# JacdacBrainNRF_57.net
KiCad netlist of a schematic drawn in Altium Designer
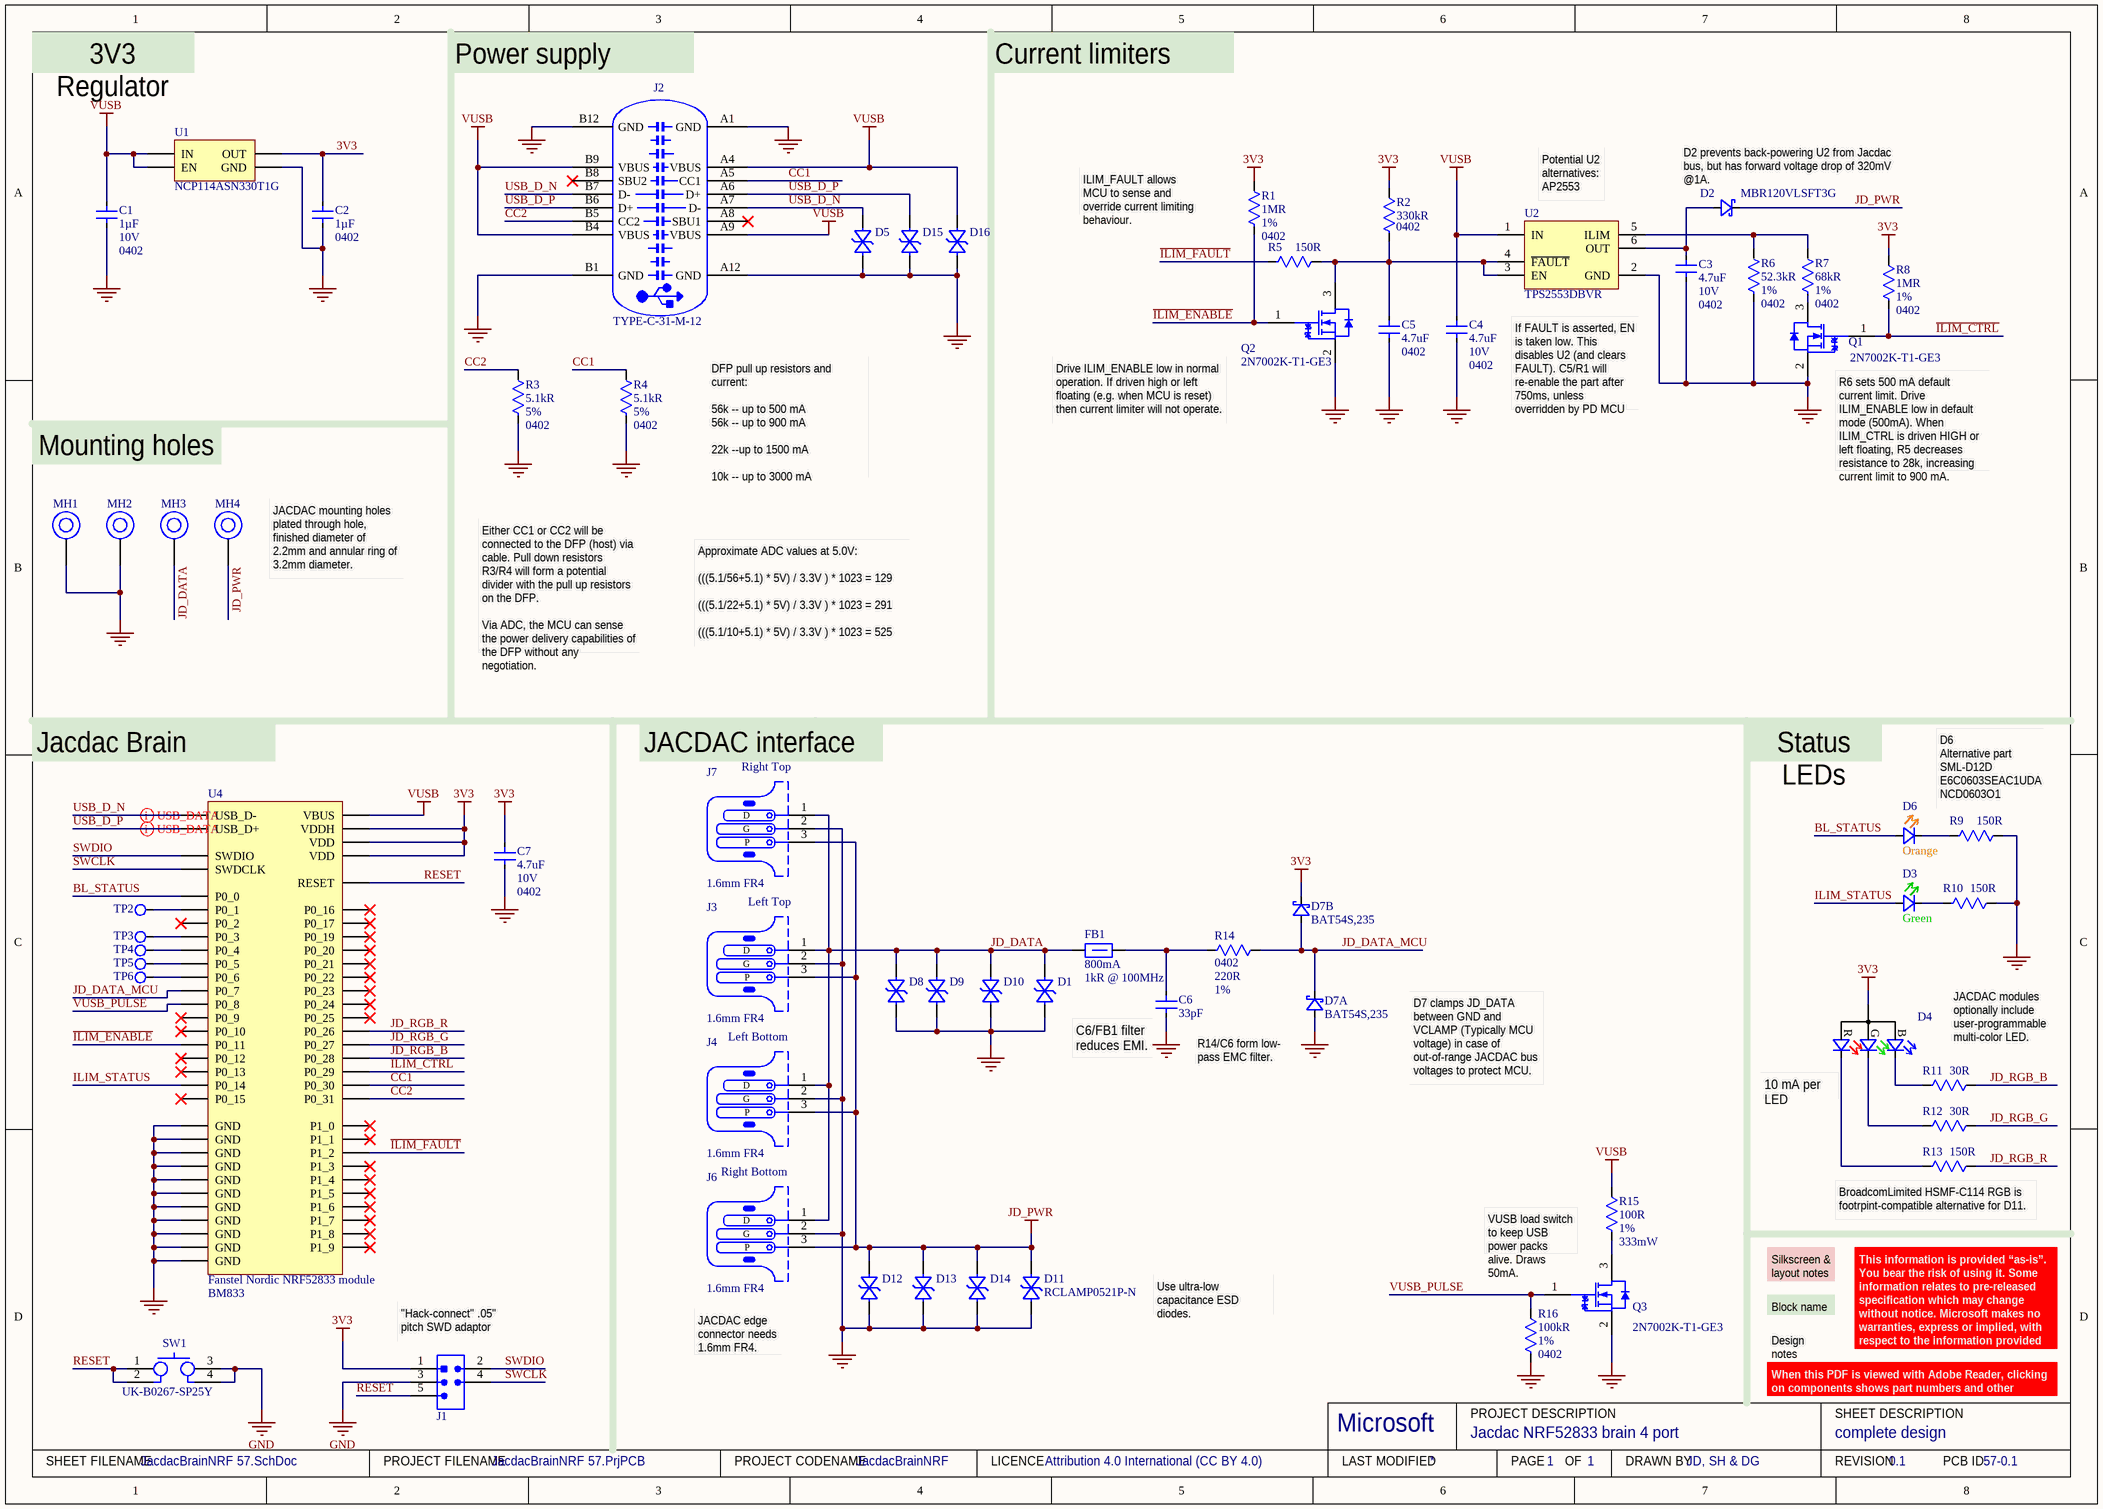
[diagram p0: JacdacBrainNRF 57.SchDoc]

(export (version "E")
  (design (tool "Eeschema 10.0.6"))
  (components
    (comp (ref "C1")
      (value "CL05A105KP5NNNC")
      (footprint "C0402_0.55MM - without outline")
      (description "CAP CER 1UF 10V X5R 0402")
      (fields
        (field (name "MANUFACTURER") "Samsung")
        (field (name "TOLERANCE") "10%")
        (field (name "CAPACITANCE") "1µF")
        (field (name "VOLTAGE RATING") "10V")
        (field (name "CASE CODE (IMPERIAL)") "0402")
        (field (name "CREATED") "DG")
        (field (name "CHECKED") "?")
      )
      (libsource (lib "Samsung") (part "CL05A105KP5NNNC"))
    )
    (comp (ref "C2")
      (value "CL05A105KP5NNNC")
      (footprint "C0402_0.55MM - without outline")
      (description "CAP CER 1UF 10V X5R 0402")
      (fields
        (field (name "MANUFACTURER") "Samsung")
        (field (name "TOLERANCE") "10%")
        (field (name "CAPACITANCE") "1µF")
        (field (name "CASE CODE (IMPERIAL)") "0402")
        (field (name "CREATED") "DG")
        (field (name "CHECKED") "?")
      )
      (libsource (lib "Samsung") (part "CL05A105KP5NNNC"))
    )
    (comp (ref "C3")
      (value "CL05A475MP5NRNC")
      (footprint "R0402 - Without outline")
      (description "CAP CER 4.7UF 10V X5R 0402")
      (fields
        (field (name "MANUFACTURER") "Samsung")
        (field (name "TOLERANCE") "20%")
        (field (name "CAPACITANCE") "4.7uF")
        (field (name "VOLTAGE RATING") "10V")
        (field (name "CASE CODE (IMPERIAL)") "0402")
        (field (name "CREATED BY") "D. Gakure")
        (field (name "CHECKED BY") "?")
      )
      (libsource (lib "Samsung") (part "CL05A475MP5NRNC"))
    )
    (comp (ref "C4")
      (value "CL05A475MP5NRNC")
      (footprint "R0402 - Without outline")
      (description "CAP CER 4.7UF 10V X5R 0402")
      (fields
        (field (name "MANUFACTURER") "Samsung")
        (field (name "TOLERANCE") "20%")
        (field (name "CAPACITANCE") "4.7uF")
        (field (name "VOLTAGE RATING") "10V")
        (field (name "CASE CODE (IMPERIAL)") "0402")
        (field (name "CREATED BY") "D. Gakure")
        (field (name "CHECKED BY") "?")
      )
      (libsource (lib "Samsung") (part "CL05A475MP5NRNC"))
    )
    (comp (ref "C5")
      (value "CL05A475MP5NRNC")
      (footprint "R0402 - Without outline")
      (description "CAP CER 4.7UF 10V X5R 0402")
      (fields
        (field (name "MANUFACTURER") "Samsung")
        (field (name "TOLERANCE") "20%")
        (field (name "CAPACITANCE") "4.7uF")
        (field (name "CASE CODE (IMPERIAL)") "0402")
        (field (name "CREATED BY") "D. Gakure")
        (field (name "CHECKED BY") "?")
      )
      (libsource (lib "Samsung") (part "CL05A475MP5NRNC"))
    )
    (comp (ref "C6")
      (value "CL05C330JB51PNC")
      (footprint "C0402_0.55MM - without outline")
      (description "CAP CER 33PF 50V NP0 0402")
      (fields
        (field (name "MANUFACTURER") "Samsung")
        (field (name "TOLERANCE") "5%")
        (field (name "CAPACITANCE") "33pF")
        (field (name "CHECKED") "?")
        (field (name "CREATED") "DG")
      )
      (libsource (lib "Samsung") (part "CL05C330JB51PNC"))
    )
    (comp (ref "C7")
      (value "CL05A475MP5NRNC")
      (footprint "R0402 - Without outline")
      (description "CAP CER 4.7UF 10V X5R 0402")
      (fields
        (field (name "MANUFACTURER") "Samsung")
        (field (name "TOLERANCE") "20%")
        (field (name "CAPACITANCE") "4.7uF")
        (field (name "VOLTAGE RATING") "10V")
        (field (name "CASE CODE (IMPERIAL)") "0402")
        (field (name "CREATED BY") "D. Gakure")
        (field (name "CHECKED BY") "?")
      )
      (libsource (lib "Samsung") (part "CL05A475MP5NRNC"))
    )
    (comp (ref "D1")
      (value "RCLAMP0521P-N")
      (footprint "TVS 0402 - L")
      (description "Bidirectional 5V (Max) 6V 16V 3.5A (8/20us) 0402 TVS RoHS")
      (fields
        (field (name "MANUFACTURER") "Born Semiconductor")
        (field (name "CREATED BY") "D Gakure")
        (field (name "CHECKED BY") "?")
      )
      (libsource (lib "BornSemiconductor") (part "RCLAMP0521P-N"))
    )
    (comp (ref "D2")
      (value "MBR120VLSFT3G")
      (footprint "MBR120VLSFT3G")
      (description "DIODE SCHOTTKY 20V 1A SOD123FL")
      (fields
        (field (name "MANUFACTURER") "ON Semiconductor")
        (field (name "MANUFACTURER PART NUMBER") "MBR120VLSFT3G")
      )
      (libsource (lib "OnSemiconductor") (part "MBR120VLSFT3G"))
    )
    (comp (ref "D3")
      (value "~")
      (footprint "0603 Green")
      (description "LED GREEN DIFFUSED 0603 SMD")
      (fields
        (field (name "MANUFACTURER") "Everlight Elec")
        (field (name "MANUFACTURER PART NUMBER") "19-217/GHC-YR1S2/3T")
        (field (name "COLOUR") "Green")
      )
      (libsource (lib "EverlightElec") (part "19-217/GHC-YR1S2/3T"))
    )
    (comp (ref "D4")
      (value "TZ-P4-1615RGBTCA1-0.55T")
      (footprint "TZ-P4-1615RGBTCA1-0.55T")
      (description "1615 Light Emitting Diodes (LED) RoHS")
      (fields
        (field (name "MANUFACTURER") "TUOZHAN")
        (field (name "CREATED BY") "D. Gakure")
        (field (name "CHECKED BY") "?")
      )
      (libsource (lib "Tuozhan") (part "TZ-P4-1615RGBTCA1-0.55T"))
    )
    (comp (ref "D5")
      (value "RCLAMP0521P-N")
      (footprint "TVS 0402 - L")
      (description "Bidirectional 5V (Max) 6V 16V 3.5A (8/20us) 0402 TVS RoHS")
      (fields
        (field (name "MANUFACTURER") "Born Semiconductor")
        (field (name "CREATED BY") "D Gakure")
        (field (name "CHECKED BY") "?")
      )
      (libsource (lib "BornSemiconductor") (part "RCLAMP0521P-N"))
    )
    (comp (ref "D6")
      (value "~")
      (footprint "0603 Orange")
      (description "LED ORANGE DIFFUSED 0603 SMD")
      (fields
        (field (name "MANUFACTURER") "Everlight Elec")
        (field (name "MANUFACTURER PART NUMBER") "19-217/S2C-AQ1R1B/3T")
        (field (name "COLOUR") "Orange")
      )
      (libsource (lib "EverlightElec") (part "19-217/S2C-AQ1R1B/3T"))
    )
    (comp (ref "D7")
      (value "BAT54S")
      (footprint "NXP-BAT54S-TO-236AB")
      (description "DIODE ARRAY SCHOTTKY 30V SOT23")
      (fields (field (name "MANUFACTURER") "Nexperia") (field (name "MANUFACTURER PART NUMBER") "BAT54S,235"))
      (libsource (lib "NXP") (part "BAT54S"))
    )
    (comp (ref "D8")
      (value "RCLAMP0521P-N")
      (footprint "TVS 0402 - L")
      (description "Bidirectional 5V (Max) 6V 16V 3.5A (8/20us) 0402 TVS RoHS")
      (fields
        (field (name "MANUFACTURER") "Born Semiconductor")
        (field (name "CREATED BY") "D Gakure")
        (field (name "CHECKED BY") "?")
      )
      (libsource (lib "BornSemiconductor") (part "RCLAMP0521P-N"))
    )
    (comp (ref "D9")
      (value "RCLAMP0521P-N")
      (footprint "TVS 0402 - L")
      (description "Bidirectional 5V (Max) 6V 16V 3.5A (8/20us) 0402 TVS RoHS")
      (fields
        (field (name "MANUFACTURER") "Born Semiconductor")
        (field (name "CREATED BY") "D Gakure")
        (field (name "CHECKED BY") "?")
      )
      (libsource (lib "BornSemiconductor") (part "RCLAMP0521P-N"))
    )
    (comp (ref "D10")
      (value "RCLAMP0521P-N")
      (footprint "TVS 0402 - L")
      (description "Bidirectional 5V (Max) 6V 16V 3.5A (8/20us) 0402 TVS RoHS")
      (fields
        (field (name "MANUFACTURER") "Born Semiconductor")
        (field (name "CREATED BY") "D Gakure")
        (field (name "CHECKED BY") "?")
      )
      (libsource (lib "BornSemiconductor") (part "RCLAMP0521P-N"))
    )
    (comp (ref "D11")
      (value "RCLAMP0521P-N")
      (footprint "TVS 0402 - L")
      (description "Bidirectional 5V (Max) 6V 16V 3.5A (8/20us) 0402 TVS RoHS")
      (fields
        (field (name "MANUFACTURER") "Born Semiconductor")
        (field (name "MANUFACTURER PART NUMBER") "RCLAMP0521P-N")
        (field (name "CREATED BY") "D Gakure")
        (field (name "CHECKED BY") "?")
      )
      (libsource (lib "BornSemiconductor") (part "RCLAMP0521P-N"))
    )
    (comp (ref "D12")
      (value "RCLAMP0521P-N")
      (footprint "TVS 0402 - L")
      (description "Bidirectional 5V (Max) 6V 16V 3.5A (8/20us) 0402 TVS RoHS")
      (fields
        (field (name "MANUFACTURER") "Born Semiconductor")
        (field (name "CREATED BY") "D Gakure")
        (field (name "CHECKED BY") "?")
      )
      (libsource (lib "BornSemiconductor") (part "RCLAMP0521P-N"))
    )
    (comp (ref "D13")
      (value "RCLAMP0521P-N")
      (footprint "TVS 0402 - L")
      (description "Bidirectional 5V (Max) 6V 16V 3.5A (8/20us) 0402 TVS RoHS")
      (fields
        (field (name "MANUFACTURER") "Born Semiconductor")
        (field (name "CREATED BY") "D Gakure")
        (field (name "CHECKED BY") "?")
      )
      (libsource (lib "BornSemiconductor") (part "RCLAMP0521P-N"))
    )
    (comp (ref "D14")
      (value "RCLAMP0521P-N")
      (footprint "TVS 0402 - L")
      (description "Bidirectional 5V (Max) 6V 16V 3.5A (8/20us) 0402 TVS RoHS")
      (fields
        (field (name "MANUFACTURER") "Born Semiconductor")
        (field (name "CREATED BY") "D Gakure")
        (field (name "CHECKED BY") "?")
      )
      (libsource (lib "BornSemiconductor") (part "RCLAMP0521P-N"))
    )
    (comp (ref "D15")
      (value "RCLAMP0521P-N")
      (footprint "TVS 0402 - L")
      (description "Bidirectional 5V (Max) 6V 16V 3.5A (8/20us) 0402 TVS RoHS")
      (fields
        (field (name "MANUFACTURER") "Born Semiconductor")
        (field (name "CREATED BY") "D Gakure")
        (field (name "CHECKED BY") "?")
      )
      (libsource (lib "BornSemiconductor") (part "RCLAMP0521P-N"))
    )
    (comp (ref "D16")
      (value "RCLAMP0521P-N")
      (footprint "TVS 0402 - L")
      (description "Bidirectional 5V (Max) 6V 16V 3.5A (8/20us) 0402 TVS RoHS")
      (fields
        (field (name "MANUFACTURER") "Born Semiconductor")
        (field (name "CREATED BY") "D Gakure")
        (field (name "CHECKED BY") "?")
      )
      (libsource (lib "BornSemiconductor") (part "RCLAMP0521P-N"))
    )
    (comp (ref "FB1")
      (value "TDK MPZ1608S102ATA00")
      (footprint "TDK MPZ1608 0.8mm - without outline")
      (description "0603 1k@100MHz 0.8A chip")
      (fields
        (field (name "TOLERANCE") "25%")
        (field (name "MANUFACTURER") "TDK")
        (field (name "CURRENT RATING") "800mA")
        (field (name "IMPEDANCE") "1kR @ 100MHz")
      )
      (libsource (lib "TDK") (part "TDK MPZ1608S102ATA00"))
    )
    (comp (ref "J1")
      (value "Hack Connect Mini 1.27 mm pitch 2-row")
      (footprint "HACK_CONNECT_MINI_5_X_1_27")
      (libsource (lib "generic-con") (part "HACK_CONNECT_MINI"))
    )
    (comp (ref "J2")
      (value "TYPE-C-31-M-12")
      (footprint "TYPE-C-31-M-12")
      (description "USB - Type C Female 16 USB Connectors RoHS")
      (fields
        (field (name "MANUFACTURER") "Korean Hroparts Elec")
        (field (name "MANUFACTURER PART NUMBER") "TYPE-C-31-M-12")
      )
      (libsource (lib "KoreanHropartsElec") (part "TYPE-C-31-M-12"))
    )
    (comp (ref "J3")
      (value "3 pin JACDAC edge connector")
      (footprint "JACDAC_EDGE_CONNECTOR_NO_TRACES")
      (description "3 pin Jacdac edge connector 1.27mm pitch")
      (fields
        (field (name "MANUFACTURER PART NUMBER") "JACDAC_EDGE_CONNECTOR")
        (field (name "PCB TYPE") "1.6mm FR4")
        (field (name "CHECKED BY") "?")
        (field (name "CREATED BY") "D. Gakure")
      )
      (libsource (lib "generic-con") (part "Jacdac edge connector"))
    )
    (comp (ref "J4")
      (value "3 pin JACDAC edge connector")
      (footprint "JACDAC_EDGE_CONNECTOR_NO_TRACES")
      (description "3 pin Jacdac edge connector 1.27mm pitch")
      (fields
        (field (name "MANUFACTURER PART NUMBER") "JACDAC_EDGE_CONNECTOR")
        (field (name "PCB TYPE") "1.6mm FR4")
        (field (name "CHECKED BY") "?")
        (field (name "CREATED BY") "D. Gakure")
      )
      (libsource (lib "generic-con") (part "Jacdac edge connector"))
    )
    (comp (ref "J6")
      (value "3 pin JACDAC edge connector")
      (footprint "JACDAC_EDGE_CONNECTOR_NO_TRACES")
      (description "3 pin Jacdac edge connector 1.27mm pitch")
      (fields
        (field (name "MANUFACTURER PART NUMBER") "JACDAC_EDGE_CONNECTOR")
        (field (name "PCB TYPE") "1.6mm FR4")
        (field (name "CHECKED BY") "?")
        (field (name "CREATED BY") "D. Gakure")
      )
      (libsource (lib "generic-con") (part "Jacdac edge connector"))
    )
    (comp (ref "J7")
      (value "3 pin JACDAC edge connector")
      (footprint "JACDAC_EDGE_CONNECTOR_NO_TRACES")
      (description "3 pin Jacdac edge connector 1.27mm pitch")
      (fields
        (field (name "MANUFACTURER PART NUMBER") "JACDAC_EDGE_CONNECTOR")
        (field (name "PCB TYPE") "1.6mm FR4")
        (field (name "CHECKED BY") "?")
        (field (name "CREATED BY") "D. Gakure")
      )
      (libsource (lib "generic-con") (part "Jacdac edge connector"))
    )
    (comp (ref "MH1")
      (value "MH_5.0MMK_3.0MMC_2.1MMD_PTH")
      (footprint "MH_5.0MMK_3.0MMC_2.1MMD_PTH")
      (description "Mounting Hole 5.0mm keepout, 3.0mm annualar ring and 2.1mm Drill PTH")
      (libsource (lib "generic") (part "MH_5.0MMK_3.0MMC_2.1MMD_PTH"))
    )
    (comp (ref "MH2")
      (value "MH_5.0MMK_3.0MMC_2.1MMD_PTH")
      (footprint "MH_5.0MMK_3.0MMC_2.1MMD_PTH")
      (description "Mounting Hole 5.0mm keepout, 3.0mm annualar ring and 2.1mm Drill PTH")
      (libsource (lib "generic") (part "MH_5.0MMK_3.0MMC_2.1MMD_PTH"))
    )
    (comp (ref "MH3")
      (value "MH_5.0MMK_3.0MMC_2.1MMD_PTH")
      (footprint "MH_5.0MMK_3.0MMC_2.1MMD_PTH")
      (description "Mounting Hole 5.0mm keepout, 3.0mm annualar ring and 2.1mm Drill PTH")
      (libsource (lib "generic") (part "MH_5.0MMK_3.0MMC_2.1MMD_PTH"))
    )
    (comp (ref "MH4")
      (value "MH_5.0MMK_3.0MMC_2.1MMD_PTH")
      (footprint "MH_5.0MMK_3.0MMC_2.1MMD_PTH")
      (description "Mounting Hole 5.0mm keepout, 3.0mm annualar ring and 2.1mm Drill PTH")
      (libsource (lib "generic") (part "MH_5.0MMK_3.0MMC_2.1MMD_PTH"))
    )
    (comp (ref "Q1")
      (value "2N7002K-T1-GE3")
      (footprint "SOT-23-3 (TO-236)")
      (description "Trans MOSFET N-CH Si 60V 0.3A 3-Pin SOT-23 T/R")
      (fields
        (field (name "MANUFACTURER") "Vishay")
        (field (name "VOLTAGE") "60V")
        (field (name "MANUFACTURER PART NUMBER") "2N7002K-T1-GE3")
      )
      (libsource (lib "Vishay") (part "2N7002K-T1-GE3"))
    )
    (comp (ref "Q2")
      (value "2N7002K-T1-GE3")
      (footprint "SOT-23-3 (TO-236)")
      (description "Trans MOSFET N-CH Si 60V 0.3A 3-Pin SOT-23 T/R")
      (fields
        (field (name "MANUFACTURER") "Vishay")
        (field (name "VOLTAGE") "60V")
        (field (name "MANUFACTURER PART NUMBER") "2N7002K-T1-GE3")
      )
      (libsource (lib "Vishay") (part "2N7002K-T1-GE3"))
    )
    (comp (ref "Q3")
      (value "2N7002K-T1-GE3")
      (footprint "SOT-23-3 (TO-236)")
      (description "Trans MOSFET N-CH Si 60V 0.3A 3-Pin SOT-23 T/R")
      (fields
        (field (name "MANUFACTURER") "Vishay")
        (field (name "VOLTAGE") "60V")
        (field (name "MANUFACTURER PART NUMBER") "2N7002K-T1-GE3")
      )
      (libsource (lib "Vishay") (part "2N7002K-T1-GE3"))
    )
    (comp (ref "R1")
      (value "~")
      (footprint "R0402 - Without outline")
      (description "RES SMD 1M OHM 1% 1/16W 0402")
      (fields
        (field (name "MANUFACTURER") "Yageo")
        (field (name "MANUFACTURER PART NUMBER") "RC0402FR-071ML")
        (field (name "RESISTANCE") "1MR")
        (field (name "TOLERANCE") "1%")
        (field (name "CASE CODE (IMPERIAL)") "0402")
        (field (name "CREATED BY") "D. Gakure")
        (field (name "CHECKED BY") "?")
      )
      (libsource (lib "Yageo") (part "RC0402FR-071ML"))
    )
    (comp (ref "R2")
      (value "RC0402FR-07330KL")
      (footprint "R0402 - Without outline")
      (description "RES SMD 330K OHM 1% 1/16W 0402")
      (fields
        (field (name "MANUFACTURER") "Yageo")
        (field (name "RESISTANCE") "330kR")
        (field (name "TOLERANCE") "1%")
        (field (name "SIZE CODE") "0402")
        (field (name "CREATED BY") "D Gakure")
        (field (name "CHECKED BY") "?")
      )
      (libsource (lib "Yageo") (part "RC0402FR-07330KL"))
    )
    (comp (ref "R3")
      (value "RC0402JR-075K1L")
      (footprint "R0402 - Without outline")
      (description "RES SMD 5.1K OHM 5% 1/16W 0402")
      (fields
        (field (name "MANUFACTURER") "Yageo")
        (field (name "RESISTANCE") "5.1kR")
        (field (name "TOLERANCE") "5%")
        (field (name "CASE CODE (IMPERIAL)") "0402")
        (field (name "CREATED BY") "D. Gakure")
        (field (name "CHECKED BY") "?")
      )
      (libsource (lib "Yageo") (part "RC0402JR-075K1L"))
    )
    (comp (ref "R4")
      (value "RC0402JR-075K1L")
      (footprint "R0402 - Without outline")
      (description "RES SMD 5.1K OHM 5% 1/16W 0402")
      (fields
        (field (name "MANUFACTURER") "Yageo")
        (field (name "RESISTANCE") "5.1kR")
        (field (name "TOLERANCE") "5%")
        (field (name "CASE CODE (IMPERIAL)") "0402")
        (field (name "CREATED BY") "D. Gakure")
        (field (name "CHECKED BY") "?")
      )
      (libsource (lib "Yageo") (part "RC0402JR-075K1L"))
    )
    (comp (ref "R5")
      (value "RC0402FR-07150RL")
      (footprint "R0402 - Without outline")
      (description "RES SMD 150 OHM 1% 1/16W 0402")
      (fields
        (field (name "MANUFACTURER") "Yageo")
        (field (name "RESISTANCE") "150R")
        (field (name "TOLERANCE") "1%")
        (field (name "CREATED BY") "D. Gakure")
        (field (name "CHECKED BY") "?")
      )
      (libsource (lib "Yageo") (part "RC0402FR-07150RL"))
    )
    (comp (ref "R6")
      (value "RC0402FR-0752K3L")
      (footprint "R0402 - Without outline")
      (description "RES SMD 52.3K OHM 1% 1/16W 0402")
      (fields
        (field (name "MANUFACTURER") "Yageo")
        (field (name "RESISTANCE") "52.3kR")
        (field (name "TOLERANCE") "1%")
        (field (name "CASE CODE (IMPERIAL)") "0402")
        (field (name "CREATED BY") "D. Gakure")
        (field (name "CHECKED BY") "?")
      )
      (libsource (lib "Yageo") (part "RC0402FR-0752K3L"))
    )
    (comp (ref "R7")
      (value "RT0402FRE0768KL")
      (footprint "R0402 - Without outline")
      (description "RES SMD 68K OHM 1% 1/16W 0402")
      (fields
        (field (name "MANUFACTURER") "Yageo")
        (field (name "RESISTANCE") "68kR")
        (field (name "TOLERANCE") "1%")
        (field (name "CASE CODE (IMPERIAL)") "0402")
        (field (name "CREATED BY") "D. Gakure")
        (field (name "CHECKED BY") "?")
      )
      (libsource (lib "Yageo") (part "RT0402FRE0768KL"))
    )
    (comp (ref "R8")
      (value "~")
      (footprint "R0402 - Without outline")
      (description "RES SMD 1M OHM 1% 1/16W 0402")
      (fields
        (field (name "MANUFACTURER") "Yageo")
        (field (name "MANUFACTURER PART NUMBER") "RC0402FR-071ML")
        (field (name "RESISTANCE") "1MR")
        (field (name "TOLERANCE") "1%")
        (field (name "CASE CODE (IMPERIAL)") "0402")
        (field (name "CREATED BY") "D. Gakure")
        (field (name "CHECKED BY") "?")
      )
      (libsource (lib "Yageo") (part "RC0402FR-071ML"))
    )
    (comp (ref "R9")
      (value "RC0402FR-07150RL")
      (footprint "R0402 - Without outline")
      (description "RES SMD 150 OHM 1% 1/16W 0402")
      (fields
        (field (name "MANUFACTURER") "Yageo")
        (field (name "RESISTANCE") "150R")
        (field (name "TOLERANCE") "1%")
        (field (name "CREATED BY") "D. Gakure")
        (field (name "CHECKED BY") "?")
      )
      (libsource (lib "Yageo") (part "RC0402FR-07150RL"))
    )
    (comp (ref "R10")
      (value "RC0402FR-07150RL")
      (footprint "R0402 - Without outline")
      (description "RES SMD 150 OHM 1% 1/16W 0402")
      (fields
        (field (name "MANUFACTURER") "Yageo")
        (field (name "RESISTANCE") "150R")
        (field (name "TOLERANCE") "1%")
        (field (name "CREATED BY") "D. Gakure")
        (field (name "CHECKED BY") "?")
      )
      (libsource (lib "Yageo") (part "RC0402FR-07150RL"))
    )
    (comp (ref "R11")
      (value "RC0402FR-0730RL")
      (footprint "R0402 - Without outline")
      (description "RES SMD 30 OHM 1% 1/16W 0402")
      (fields
        (field (name "MANUFACTURER") "Yageo")
        (field (name "RESISTANCE") "30R")
        (field (name "TOLERANCE") "1%")
        (field (name "CREATED BY") "D. Gakure")
        (field (name "CHECKED BY") "?")
      )
      (libsource (lib "Yageo") (part "RC0402FR-0730RL"))
    )
    (comp (ref "R12")
      (value "RC0402FR-0730RL")
      (footprint "R0402 - Without outline")
      (description "RES SMD 30 OHM 1% 1/16W 0402")
      (fields
        (field (name "MANUFACTURER") "Yageo")
        (field (name "RESISTANCE") "30R")
        (field (name "TOLERANCE") "1%")
        (field (name "CREATED BY") "D. Gakure")
        (field (name "CHECKED BY") "?")
      )
      (libsource (lib "Yageo") (part "RC0402FR-0730RL"))
    )
    (comp (ref "R13")
      (value "RC0402FR-07150RL")
      (footprint "R0402 - Without outline")
      (description "RES SMD 150 OHM 1% 1/16W 0402")
      (fields
        (field (name "MANUFACTURER") "Yageo")
        (field (name "RESISTANCE") "150R")
        (field (name "TOLERANCE") "1%")
        (field (name "CREATED BY") "D. Gakure")
        (field (name "CHECKED BY") "?")
      )
      (libsource (lib "Yageo") (part "RC0402FR-07150RL"))
    )
    (comp (ref "R14")
      (value "RC0402FR-07220RL")
      (footprint "R0402 - Without outline")
      (description "RES SMD 220 OHM 1% 1/16W 0402")
      (fields
        (field (name "MANUFACTURER") "Yageo")
        (field (name "CASE CODE (IMPERIAL)") "0402")
        (field (name "RESISTANCE") "220R")
        (field (name "TOLERANCE") "1%")
        (field (name "CREATED") "D.G")
        (field (name "CHECKED") "?")
      )
      (libsource (lib "Yageo") (part "RC0402FR-07220RL"))
    )
    (comp (ref "R15")
      (value "CRGP0805F100R")
      (footprint "RES0805")
      (description "100 Ohms ±1% 0.333W, 1/3W Chip Resistor 0805 (2012 Metric) Pulse Withstanding Thick Film")
      (fields
        (field (name "MANUFACTURER") "TE Connectivity")
        (field (name "RESISTANCE") "100R")
        (field (name "TOLERANCE") "1%")
        (field (name "MAX POWER DISSIPATION") "333mW")
        (field (name "CREATED BY") "D. Gakure")
        (field (name "CHECKED BY") "?")
      )
      (libsource (lib "TEConnectivity") (part "CRGP0805F100R"))
    )
    (comp (ref "R16")
      (value "RC0402FR-07100KL")
      (footprint "R0402 - Without outline")
      (description "RES SMD 100K OHM 1% 1/16W 0402")
      (fields
        (field (name "MANUFACTURER") "Yageo")
        (field (name "RESISTANCE") "100kR")
        (field (name "TOLERANCE") "1%")
        (field (name "CASE/PACKAGE") "0402")
        (field (name "CREATED BY") "DG")
        (field (name "CHECKED BY") "?")
      )
      (libsource (lib "Yageo") (part "RC0402FR-07100KL"))
    )
    (comp (ref "SW1")
      (value "UK-B0267-SP25Y")
      (footprint "USAKRO-UK-B0267-SP25Y")
      (description "SWITCH TACTILE SSPST 50mA @ 12VDC")
      (fields
        (field (name "MANUFACTURER") "USAKRO")
        (field (name "MANUFACTURER PART NUMBER") "UK-B0267-SP25Y")
      )
      (libsource (lib "Usakro") (part "UK-B0267-SP25Y"))
    )
    (comp (ref "TP2")
      (value "TestPoint")
      (footprint "Pad1.27mm")
      (description "Test Point")
      (libsource (lib "generic") (part "TestPoint"))
    )
    (comp (ref "TP3")
      (value "TestPoint")
      (footprint "Pad1.27mm")
      (description "Test Point")
      (libsource (lib "generic") (part "TestPoint"))
    )
    (comp (ref "TP4")
      (value "TestPoint")
      (footprint "Pad1.27mm")
      (description "Test Point")
      (libsource (lib "generic") (part "TestPoint"))
    )
    (comp (ref "TP5")
      (value "TestPoint")
      (footprint "Pad1.27mm")
      (description "Test Point")
      (libsource (lib "generic") (part "TestPoint"))
    )
    (comp (ref "TP6")
      (value "TestPoint")
      (footprint "Pad1.27mm")
      (description "Test Point")
      (libsource (lib "generic") (part "TestPoint"))
    )
    (comp (ref "U1")
      (value "LDO 3.3V/300 mA")
      (footprint "ON_SEMI-SOT23-5 - without outline")
      (fields
        (field (name "MANUFACTURER") "ON Semiconductor")
        (field (name "MANUFACTURER PART NUMBER") "NCP114ASN330T1G")
        (field (name "CREATED") "DG")
        (field (name "CHECKED") "?")
      )
      (libsource (lib "OnSemiconductor") (part "NCP114ASN330T1G"))
    )
    (comp (ref "U2")
      (value "TPS2553DBVR")
      (footprint "TI-TPS2553")
      (description "IC PWR SWITCH N-CHAN 1:1 SOT23-6")
      (fields
        (field (name "MANUFACTURER") "Texas Instruments")
        (field (name "MANUFACTURER PART NUMBER") "TPS2553DBVR")
      )
      (libsource (lib "TexasInstruments") (part "TPS2553DBVR"))
    )
    (comp (ref "U4")
      (value "Fanstel Nordic NRF52833 module")
      (footprint "FANSTEL_BM833:BM833")
      (description "Fanstel Nordic nRF52833 module")
      (fields (field (name "MANUFACTURER PART NUMBER 1") "BM833"))
      (libsource (lib "Fanstel") (part "BM833"))
    )
  )
  (nets
    (net (code "1") (name "/BL_STATUS") (class "Default")
      (node (ref "D6") (pin "2") (pinfunction "A_2") (pintype "passive"))
      (node (ref "U4") (pin "16") (pinfunction "P0_0_16") (pintype "passive"))
    )
    (net (code "2") (name "/CC1") (class "Default")
      (node (ref "J2") (pin "A5") (pinfunction "CC1_A5") (pintype "passive"))
      (node (ref "R4") (pin "1") (pinfunction "1_1") (pintype "passive"))
      (node (ref "U4") (pin "11") (pinfunction "P0_30_11") (pintype "passive"))
    )
    (net (code "3") (name "/CC2") (class "Default")
      (node (ref "J2") (pin "B5") (pinfunction "CC2_B5") (pintype "passive"))
      (node (ref "R3") (pin "1") (pinfunction "1_1") (pintype "passive"))
      (node (ref "U4") (pin "12") (pinfunction "P0_31_12") (pintype "passive"))
    )
    (net (code "4") (name "/ILIM_STATUS") (class "Default")
      (node (ref "D3") (pin "2") (pinfunction "A_2") (pintype "passive"))
      (node (ref "U4") (pin "33") (pinfunction "P0_14_33") (pintype "passive"))
    )
    (net (code "5") (name "/JD_DATA") (class "Default")
      (node (ref "D1") (pin "1") (pinfunction "K_1") (pintype "passive"))
      (node (ref "D10") (pin "1") (pinfunction "K_1") (pintype "passive"))
      (node (ref "D8") (pin "1") (pinfunction "K_1") (pintype "passive"))
      (node (ref "D9") (pin "1") (pinfunction "K_1") (pintype "passive"))
      (node (ref "FB1") (pin "1") (pinfunction "1_1") (pintype "passive"))
      (node (ref "J3") (pin "1") (pinfunction "D_1") (pintype "passive"))
      (node (ref "J4") (pin "1") (pinfunction "D_1") (pintype "passive"))
      (node (ref "J6") (pin "1") (pinfunction "D_1") (pintype "passive"))
      (node (ref "J7") (pin "1") (pinfunction "D_1") (pintype "passive"))
      (node (ref "MH3") (pin "1") (pinfunction "1_1") (pintype "passive"))
    )
    (net (code "6") (name "/JD_DATA_MCU") (class "Default")
      (node (ref "D7") (pin "3") (pinfunction "K_3") (pintype "passive"))
      (node (ref "R14") (pin "1") (pinfunction "1_1") (pintype "passive"))
      (node (ref "U4") (pin "24") (pinfunction "P0_7_24") (pintype "passive"))
    )
    (net (code "7") (name "/JD_RGB_B") (class "Default")
      (node (ref "R11") (pin "2") (pinfunction "2_2") (pintype "passive"))
      (node (ref "U4") (pin "9") (pinfunction "P0_28_9") (pintype "passive"))
    )
    (net (code "8") (name "/JD_RGB_G") (class "Default")
      (node (ref "R12") (pin "2") (pinfunction "2_2") (pintype "passive"))
      (node (ref "U4") (pin "8") (pinfunction "P0_27_8") (pintype "passive"))
    )
    (net (code "9") (name "/JD_RGB_R") (class "Default")
      (node (ref "R13") (pin "2") (pinfunction "2_2") (pintype "passive"))
      (node (ref "U4") (pin "7") (pinfunction "P0_26_7") (pintype "passive"))
    )
    (net (code "10") (name "/RESET") (class "Default")
      (node (ref "J1") (pin "5") (pinfunction "RESET_5") (pintype "passive"))
      (node (ref "SW1") (pin "1") (pinfunction "1_1") (pintype "passive"))
      (node (ref "SW1") (pin "2") (pinfunction "2_2") (pintype "passive"))
      (node (ref "U4") (pin "40") (pinfunction "RESET_40") (pintype "passive"))
    )
    (net (code "11") (name "/SWCLK") (class "Default")
      (node (ref "J1") (pin "4") (pinfunction "SWCLK_4") (pintype "passive"))
      (node (ref "U4") (pin "42") (pinfunction "SWDCLK_42") (pintype "passive"))
    )
    (net (code "12") (name "/SWDIO") (class "Default")
      (node (ref "J1") (pin "2") (pinfunction "SWDIO_2") (pintype "passive"))
      (node (ref "U4") (pin "43") (pinfunction "SWDIO_43") (pintype "passive"))
    )
    (net (code "13") (name "/USB_D_N") (class "Default")
      (node (ref "D5") (pin "1") (pinfunction "K_1") (pintype "passive"))
      (node (ref "J2") (pin "A7") (pinfunction "D-_A7") (pintype "passive"))
      (node (ref "J2") (pin "B7") (pinfunction "D-_B7") (pintype "passive"))
      (node (ref "U4") (pin "68") (pinfunction "USB_D-_68") (pintype "passive"))
    )
    (net (code "14") (name "/USB_D_P") (class "Default")
      (node (ref "D15") (pin "1") (pinfunction "K_1") (pintype "passive"))
      (node (ref "J2") (pin "A6") (pinfunction "D+_A6") (pintype "passive"))
      (node (ref "J2") (pin "B6") (pinfunction "D+_B6") (pintype "passive"))
      (node (ref "U4") (pin "67") (pinfunction "USB_D+_67") (pintype "passive"))
    )
    (net (code "15") (name "/VUSB_PULSE") (class "Default")
      (node (ref "Q3") (pin "1") (pinfunction "G_1") (pintype "passive"))
      (node (ref "R16") (pin "2") (pinfunction "2_2") (pintype "passive"))
      (node (ref "U4") (pin "27") (pinfunction "P0_8_27") (pintype "passive"))
    )
    (net (code "16") (name "/~{ILIM_CTRL}") (class "Default")
      (node (ref "Q1") (pin "1") (pinfunction "G_1") (pintype "passive"))
      (node (ref "R8") (pin "2") (pinfunction "2_2") (pintype "passive"))
      (node (ref "U4") (pin "10") (pinfunction "P0_29_10") (pintype "passive"))
    )
    (net (code "17") (name "/~{ILIM_ENABLE}") (class "Default")
      (node (ref "Q2") (pin "1") (pinfunction "G_1") (pintype "passive"))
      (node (ref "R1") (pin "2") (pinfunction "2_2") (pintype "passive"))
      (node (ref "U4") (pin "34") (pinfunction "P0_11_34") (pintype "passive"))
    )
    (net (code "18") (name "/~{ILIM_FAULT}") (class "Default")
      (node (ref "R5") (pin "1") (pinfunction "1_1") (pintype "passive"))
      (node (ref "U4") (pin "32") (pinfunction "P1_2_32") (pintype "passive"))
    )
    (net (code "19") (name "3V3") (class "Default")
      (node (ref "C2") (pin "2") (pinfunction "2_2") (pintype "passive"))
      (node (ref "C7") (pin "2") (pinfunction "2_2") (pintype "passive"))
      (node (ref "D4") (pin "1") (pinfunction "A_1") (pintype "passive"))
      (node (ref "D7") (pin "2") (pinfunction "K_2") (pintype "passive"))
      (node (ref "J1") (pin "1") (pinfunction "VCC_1") (pintype "passive"))
      (node (ref "R1") (pin "1") (pinfunction "1_1") (pintype "passive"))
      (node (ref "R2") (pin "1") (pinfunction "1_1") (pintype "passive"))
      (node (ref "R8") (pin "1") (pinfunction "1_1") (pintype "passive"))
      (node (ref "U1") (pin "5") (pinfunction "OUT_5") (pintype "passive"))
      (node (ref "U4") (pin "14") (pinfunction "VDD_14") (pintype "passive"))
      (node (ref "U4") (pin "28") (pinfunction "VDD_28") (pintype "passive"))
      (node (ref "U4") (pin "56") (pinfunction "VDDH_56") (pintype "passive"))
    )
    (net (code "20") (name "GND") (class "Default")
      (node (ref "C1") (pin "1") (pinfunction "1_1") (pintype "passive"))
      (node (ref "C2") (pin "1") (pinfunction "1_1") (pintype "passive"))
      (node (ref "C3") (pin "1") (pinfunction "1_1") (pintype "passive"))
      (node (ref "C4") (pin "1") (pinfunction "1_1") (pintype "passive"))
      (node (ref "C5") (pin "1") (pinfunction "1_1") (pintype "passive"))
      (node (ref "C6") (pin "1") (pinfunction "1_1") (pintype "passive"))
      (node (ref "C7") (pin "1") (pinfunction "1_1") (pintype "passive"))
      (node (ref "D1") (pin "2") (pinfunction "A_2") (pintype "passive"))
      (node (ref "D10") (pin "2") (pinfunction "A_2") (pintype "passive"))
      (node (ref "D11") (pin "2") (pinfunction "A_2") (pintype "passive"))
      (node (ref "D12") (pin "2") (pinfunction "A_2") (pintype "passive"))
      (node (ref "D13") (pin "2") (pinfunction "A_2") (pintype "passive"))
      (node (ref "D14") (pin "2") (pinfunction "A_2") (pintype "passive"))
      (node (ref "D15") (pin "2") (pinfunction "A_2") (pintype "passive"))
      (node (ref "D16") (pin "2") (pinfunction "A_2") (pintype "passive"))
      (node (ref "D5") (pin "2") (pinfunction "A_2") (pintype "passive"))
      (node (ref "D7") (pin "1") (pinfunction "A_1") (pintype "passive"))
      (node (ref "D8") (pin "2") (pinfunction "A_2") (pintype "passive"))
      (node (ref "D9") (pin "2") (pinfunction "A_2") (pintype "passive"))
      (node (ref "J1") (pin "3") (pinfunction "GND_3") (pintype "passive"))
      (node (ref "J2") (pin "A1") (pinfunction "GND_A1") (pintype "passive"))
      (node (ref "J2") (pin "A12") (pinfunction "GND_A12") (pintype "passive"))
      (node (ref "J2") (pin "B1") (pinfunction "GND_B1") (pintype "passive"))
      (node (ref "J2") (pin "B12") (pinfunction "GND_B12") (pintype "passive"))
      (node (ref "J3") (pin "2") (pinfunction "G_2") (pintype "passive"))
      (node (ref "J4") (pin "2") (pinfunction "G_2") (pintype "passive"))
      (node (ref "J6") (pin "2") (pinfunction "G_2") (pintype "passive"))
      (node (ref "J7") (pin "2") (pinfunction "G_2") (pintype "passive"))
      (node (ref "MH1") (pin "1") (pinfunction "1_1") (pintype "passive"))
      (node (ref "MH2") (pin "1") (pinfunction "1_1") (pintype "passive"))
      (node (ref "Q1") (pin "2") (pinfunction "S_2") (pintype "passive"))
      (node (ref "Q2") (pin "2") (pinfunction "S_2") (pintype "passive"))
      (node (ref "Q3") (pin "2") (pinfunction "S_2") (pintype "passive"))
      (node (ref "R10") (pin "2") (pinfunction "2_2") (pintype "passive"))
      (node (ref "R16") (pin "1") (pinfunction "1_1") (pintype "passive"))
      (node (ref "R3") (pin "2") (pinfunction "2_2") (pintype "passive"))
      (node (ref "R4") (pin "2") (pinfunction "2_2") (pintype "passive"))
      (node (ref "R6") (pin "1") (pinfunction "1_1") (pintype "passive"))
      (node (ref "R9") (pin "2") (pinfunction "2_2") (pintype "passive"))
      (node (ref "SW1") (pin "3") (pinfunction "3_3") (pintype "passive"))
      (node (ref "SW1") (pin "4") (pinfunction "4_4") (pintype "passive"))
      (node (ref "U1") (pin "2") (pinfunction "GND_2") (pintype "passive"))
      (node (ref "U2") (pin "2") (pinfunction "GND_2") (pintype "passive"))
      (node (ref "U4") (pin "1") (pinfunction "GND_1") (pintype "passive"))
      (node (ref "U4") (pin "13") (pinfunction "GND_13") (pintype "passive"))
      (node (ref "U4") (pin "15") (pinfunction "GND_15") (pintype "passive"))
      (node (ref "U4") (pin "18") (pinfunction "GND_18") (pintype "passive"))
      (node (ref "U4") (pin "19") (pinfunction "GND_19") (pintype "passive"))
      (node (ref "U4") (pin "2") (pinfunction "GND_2") (pintype "passive"))
      (node (ref "U4") (pin "3") (pinfunction "GND_3") (pintype "passive"))
      (node (ref "U4") (pin "30") (pinfunction "GND_30") (pintype "passive"))
      (node (ref "U4") (pin "4") (pinfunction "GND_4") (pintype "passive"))
      (node (ref "U4") (pin "45") (pinfunction "GND_45") (pintype "passive"))
      (node (ref "U4") (pin "5") (pinfunction "GND_5") (pintype "passive"))
    )
    (net (code "21") (name "JD_PWR") (class "Default")
      (node (ref "D11") (pin "1") (pinfunction "K_1") (pintype "passive"))
      (node (ref "D12") (pin "1") (pinfunction "K_1") (pintype "passive"))
      (node (ref "D13") (pin "1") (pinfunction "K_1") (pintype "passive"))
      (node (ref "D14") (pin "1") (pinfunction "K_1") (pintype "passive"))
      (node (ref "D2") (pin "1") (pinfunction "K_1") (pintype "passive"))
      (node (ref "J3") (pin "3") (pinfunction "P_3") (pintype "passive"))
      (node (ref "J4") (pin "3") (pinfunction "P_3") (pintype "passive"))
      (node (ref "J6") (pin "3") (pinfunction "P_3") (pintype "passive"))
      (node (ref "J7") (pin "3") (pinfunction "P_3") (pintype "passive"))
      (node (ref "MH4") (pin "1") (pinfunction "1_1") (pintype "passive"))
    )
    (net (code "22") (name "Net-(C6-Pad2)") (class "Default")
      (node (ref "C6") (pin "2") (pinfunction "2_2") (pintype "passive"))
      (node (ref "FB1") (pin "2") (pinfunction "2_2") (pintype "passive"))
      (node (ref "R14") (pin "2") (pinfunction "2_2") (pintype "passive"))
    )
    (net (code "23") (name "Net-(D2-A)") (class "Default")
      (node (ref "C3") (pin "2") (pinfunction "2_2") (pintype "passive"))
      (node (ref "D2") (pin "2") (pinfunction "A_2") (pintype "passive"))
      (node (ref "U2") (pin "6") (pinfunction "OUT_6") (pintype "passive"))
    )
    (net (code "24") (name "Net-(D3-K)") (class "Default")
      (node (ref "D3") (pin "1") (pinfunction "K_1") (pintype "passive"))
      (node (ref "R10") (pin "1") (pinfunction "1_1") (pintype "passive"))
    )
    (net (code "25") (name "Net-(D4-B)") (class "Default")
      (node (ref "D4") (pin "4") (pinfunction "B_4") (pintype "passive"))
      (node (ref "R11") (pin "1") (pinfunction "1_1") (pintype "passive"))
    )
    (net (code "26") (name "Net-(D4-G)") (class "Default")
      (node (ref "D4") (pin "3") (pinfunction "G_3") (pintype "passive"))
      (node (ref "R12") (pin "1") (pinfunction "1_1") (pintype "passive"))
    )
    (net (code "27") (name "Net-(D4-R)") (class "Default")
      (node (ref "D4") (pin "2") (pinfunction "R_2") (pintype "passive"))
      (node (ref "R13") (pin "1") (pinfunction "1_1") (pintype "passive"))
    )
    (net (code "28") (name "Net-(D6-K)") (class "Default")
      (node (ref "D6") (pin "1") (pinfunction "K_1") (pintype "passive"))
      (node (ref "R9") (pin "1") (pinfunction "1_1") (pintype "passive"))
    )
    (net (code "29") (name "Net-(Q1-D)") (class "Default")
      (node (ref "Q1") (pin "3") (pinfunction "D_3") (pintype "passive"))
      (node (ref "R7") (pin "1") (pinfunction "1_1") (pintype "passive"))
    )
    (net (code "30") (name "Net-(Q2-D)") (class "Default")
      (node (ref "C5") (pin "2") (pinfunction "2_2") (pintype "passive"))
      (node (ref "Q2") (pin "3") (pinfunction "D_3") (pintype "passive"))
      (node (ref "R2") (pin "2") (pinfunction "2_2") (pintype "passive"))
      (node (ref "R5") (pin "2") (pinfunction "2_2") (pintype "passive"))
      (node (ref "U2") (pin "3") (pinfunction "EN_3") (pintype "passive"))
      (node (ref "U2") (pin "4") (pinfunction "~{FAULT}_4") (pintype "passive"))
    )
    (net (code "31") (name "Net-(Q3-D)") (class "Default")
      (node (ref "Q3") (pin "3") (pinfunction "D_3") (pintype "passive"))
      (node (ref "R15") (pin "1") (pinfunction "1_1") (pintype "passive"))
    )
    (net (code "32") (name "Net-(U2-ILIM)") (class "Default")
      (node (ref "R6") (pin "2") (pinfunction "2_2") (pintype "passive"))
      (node (ref "R7") (pin "2") (pinfunction "2_2") (pintype "passive"))
      (node (ref "U2") (pin "5") (pinfunction "ILIM_5") (pintype "passive"))
    )
    (net (code "33") (name "Net-(U4-P0_1)") (class "Default")
      (node (ref "TP2") (pin "1") (pinfunction "1_1") (pintype "passive"))
      (node (ref "U4") (pin "17") (pinfunction "P0_1_17") (pintype "passive"))
    )
    (net (code "34") (name "Net-(U4-P0_3)") (class "Default")
      (node (ref "TP3") (pin "1") (pinfunction "1_1") (pintype "passive"))
      (node (ref "U4") (pin "20") (pinfunction "P0_3_20") (pintype "passive"))
    )
    (net (code "35") (name "Net-(U4-P0_4)") (class "Default")
      (node (ref "TP4") (pin "1") (pinfunction "1_1") (pintype "passive"))
      (node (ref "U4") (pin "21") (pinfunction "P0_4_21") (pintype "passive"))
    )
    (net (code "36") (name "Net-(U4-P0_5)") (class "Default")
      (node (ref "TP5") (pin "1") (pinfunction "1_1") (pintype "passive"))
      (node (ref "U4") (pin "23") (pinfunction "P0_5_23") (pintype "passive"))
    )
    (net (code "37") (name "Net-(U4-P0_6)") (class "Default")
      (node (ref "TP6") (pin "1") (pinfunction "1_1") (pintype "passive"))
      (node (ref "U4") (pin "25") (pinfunction "P0_6_25") (pintype "passive"))
    )
    (net (code "38") (name "VUSB") (class "Default")
      (node (ref "C1") (pin "2") (pinfunction "2_2") (pintype "passive"))
      (node (ref "C4") (pin "2") (pinfunction "2_2") (pintype "passive"))
      (node (ref "D16") (pin "1") (pinfunction "K_1") (pintype "passive"))
      (node (ref "J2") (pin "A4") (pinfunction "VBUS_A4") (pintype "passive"))
      (node (ref "J2") (pin "A9") (pinfunction "VBUS_A9") (pintype "passive"))
      (node (ref "J2") (pin "B4") (pinfunction "VBUS_B4") (pintype "passive"))
      (node (ref "J2") (pin "B9") (pinfunction "VBUS_B9") (pintype "passive"))
      (node (ref "R15") (pin "2") (pinfunction "2_2") (pintype "passive"))
      (node (ref "U1") (pin "1") (pinfunction "IN_1") (pintype "passive"))
      (node (ref "U1") (pin "3") (pinfunction "EN_3") (pintype "passive"))
      (node (ref "U2") (pin "1") (pinfunction "IN_1") (pintype "passive"))
      (node (ref "U4") (pin "58") (pinfunction "VBUS_58") (pintype "passive"))
    )
    (net (code "39") (name "unconnected-(J2-SBU1-PadA8)") (class "Default")
      (node (ref "J2") (pin "A8") (pinfunction "SBU1_A8") (pintype "passive+no_connect"))
    )
    (net (code "40") (name "unconnected-(J2-SBU2-PadB8)") (class "Default")
      (node (ref "J2") (pin "B8") (pinfunction "SBU2_B8") (pintype "passive+no_connect"))
    )
    (net (code "41") (name "unconnected-(U4-P0_2-Pad22)") (class "Default")
      (node (ref "U4") (pin "22") (pinfunction "P0_2_22") (pintype "passive+no_connect"))
    )
    (net (code "42") (name "unconnected-(U4-P0_9-Pad26)") (class "Default")
      (node (ref "U4") (pin "26") (pinfunction "P0_9_26") (pintype "passive+no_connect"))
    )
    (net (code "43") (name "unconnected-(U4-P0_10-Pad29)") (class "Default")
      (node (ref "U4") (pin "29") (pinfunction "P0_10_29") (pintype "passive+no_connect"))
    )
    (net (code "44") (name "unconnected-(U4-P0_12-Pad64)") (class "Default")
      (node (ref "U4") (pin "64") (pinfunction "P0_12_64") (pintype "passive+no_connect"))
    )
    (net (code "45") (name "unconnected-(U4-P0_13-Pad41)") (class "Default")
      (node (ref "U4") (pin "41") (pinfunction "P0_13_41") (pintype "passive+no_connect"))
    )
    (net (code "46") (name "unconnected-(U4-P0_15-Pad35)") (class "Default")
      (node (ref "U4") (pin "35") (pinfunction "P0_15_35") (pintype "passive+no_connect"))
    )
    (net (code "47") (name "unconnected-(U4-P0_16-Pad36)") (class "Default")
      (node (ref "U4") (pin "36") (pinfunction "P0_16_36") (pintype "passive+no_connect"))
    )
    (net (code "48") (name "unconnected-(U4-P0_17-Pad37)") (class "Default")
      (node (ref "U4") (pin "37") (pinfunction "P0_17_37") (pintype "passive+no_connect"))
    )
    (net (code "49") (name "unconnected-(U4-P0_19-Pad48)") (class "Default")
      (node (ref "U4") (pin "48") (pinfunction "P0_19_48") (pintype "passive+no_connect"))
    )
    (net (code "50") (name "unconnected-(U4-P0_20-Pad62)") (class "Default")
      (node (ref "U4") (pin "62") (pinfunction "P0_20_62") (pintype "passive+no_connect"))
    )
    (net (code "51") (name "unconnected-(U4-P0_21-Pad60)") (class "Default")
      (node (ref "U4") (pin "60") (pinfunction "P0_21_60") (pintype "passive+no_connect"))
    )
    (net (code "52") (name "unconnected-(U4-P0_22-Pad44)") (class "Default")
      (node (ref "U4") (pin "44") (pinfunction "P0_22_44") (pintype "passive+no_connect"))
    )
    (net (code "53") (name "unconnected-(U4-P0_23-Pad53)") (class "Default")
      (node (ref "U4") (pin "53") (pinfunction "P0_23_53") (pintype "passive+no_connect"))
    )
    (net (code "54") (name "unconnected-(U4-P0_24-Pad47)") (class "Default")
      (node (ref "U4") (pin "47") (pinfunction "P0_24_47") (pintype "passive+no_connect"))
    )
    (net (code "55") (name "unconnected-(U4-P0_25-Pad55)") (class "Default")
      (node (ref "U4") (pin "55") (pinfunction "P0_25_55") (pintype "passive+no_connect"))
    )
    (net (code "56") (name "unconnected-(U4-P1_0-Pad38)") (class "Default")
      (node (ref "U4") (pin "38") (pinfunction "P1_0_38") (pintype "passive+no_connect"))
    )
    (net (code "57") (name "unconnected-(U4-P1_1-Pad31)") (class "Default")
      (node (ref "U4") (pin "31") (pinfunction "P1_1_31") (pintype "passive+no_connect"))
    )
    (net (code "58") (name "unconnected-(U4-P1_3-Pad49)") (class "Default")
      (node (ref "U4") (pin "49") (pinfunction "P1_3_49") (pintype "passive+no_connect"))
    )
    (net (code "59") (name "unconnected-(U4-P1_4-Pad61)") (class "Default")
      (node (ref "U4") (pin "61") (pinfunction "P1_4_61") (pintype "passive+no_connect"))
    )
    (net (code "60") (name "unconnected-(U4-P1_5-Pad51)") (class "Default")
      (node (ref "U4") (pin "51") (pinfunction "P1_5_51") (pintype "passive+no_connect"))
    )
    (net (code "61") (name "unconnected-(U4-P1_6-Pad65)") (class "Default")
      (node (ref "U4") (pin "65") (pinfunction "P1_6_65") (pintype "passive+no_connect"))
    )
    (net (code "62") (name "unconnected-(U4-P1_7-Pad66)") (class "Default")
      (node (ref "U4") (pin "66") (pinfunction "P1_7_66") (pintype "passive+no_connect"))
    )
    (net (code "63") (name "unconnected-(U4-P1_8-Pad54)") (class "Default")
      (node (ref "U4") (pin "54") (pinfunction "P1_8_54") (pintype "passive+no_connect"))
    )
    (net (code "64") (name "unconnected-(U4-P1_9-Pad52)") (class "Default")
      (node (ref "U4") (pin "52") (pinfunction "P1_9_52") (pintype "passive+no_connect"))
    )
  )
)
